# rocketpin.net
KiCad netlist of a schematic drawn in EAGLE
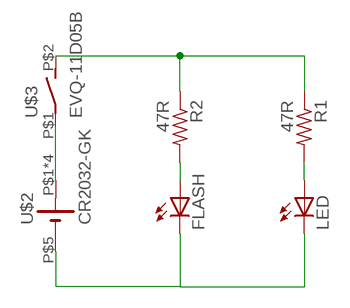
[diagram p0: schematic, sheet 1]

(export (version "E")
  (design (tool "Eeschema 10.0.6"))
  (components
    (comp (ref "FLASH")
      (value "LED5MM")
      (footprint "eagle-import:LED5MM")
      (libsource (lib "eagle-import") (part "LED5MM"))
    )
    (comp (ref "LED")
      (value "LED5MM")
      (footprint "eagle-import:LED5MM")
      (libsource (lib "eagle-import") (part "LED5MM"))
    )
    (comp (ref "R1")
      (value "47R")
      (footprint "eagle-import:0207_10")
      (libsource (lib "eagle-import") (part "R-US_0207/10"))
    )
    (comp (ref "R2")
      (value "47R")
      (footprint "eagle-import:0207_10")
      (libsource (lib "eagle-import") (part "R-US_0207/10"))
    )
    (comp (ref "U$2")
      (value "CR2032-GK")
      (footprint "eagle-import:BAT-HLD-001-THM")
      (libsource (lib "eagle-import") (part "CR2032-GK"))
    )
    (comp (ref "U$3")
      (value "EVQ-11D05B")
      (footprint "eagle-import:SPST-5MM")
      (libsource (lib "eagle-import") (part "EVQ-11D05B"))
    )
  )
  (nets
    (net (code "1") (name "Net-(FLASH-C)") (class "Default")
      (node (ref "FLASH") (pin "K") (pinfunction "C_K") (pintype "passive"))
      (node (ref "LED") (pin "K") (pinfunction "C_K") (pintype "passive"))
      (node (ref "U$2") (pin "P$5") (pinfunction "-_P$5") (pintype "passive"))
    )
    (net (code "2") (name "Net-(FLASH-PadA)") (class "Default")
      (node (ref "FLASH") (pin "A") (pinfunction "A_A") (pintype "passive"))
      (node (ref "R2") (pin "2") (pinfunction "2_2") (pintype "passive"))
    )
    (net (code "3") (name "Net-(LED-PadA)") (class "Default")
      (node (ref "LED") (pin "A") (pinfunction "A_A") (pintype "passive"))
      (node (ref "R1") (pin "2") (pinfunction "2_2") (pintype "passive"))
    )
    (net (code "4") (name "Net-(U$3-P)") (class "Default")
      (node (ref "U$2") (pin "P$1") (pinfunction "+_P$1") (pintype "passive"))
      (node (ref "U$2") (pin "P$2") (pinfunction "+_P$2") (pintype "passive"))
      (node (ref "U$2") (pin "P$3") (pinfunction "+_P$3") (pintype "passive"))
      (node (ref "U$2") (pin "P$4") (pinfunction "+_P$4") (pintype "passive"))
      (node (ref "U$3") (pin "P$1") (pinfunction "P_P$1") (pintype "passive"))
    )
    (net (code "5") (name "Net-(U$3-S)") (class "Default")
      (node (ref "R1") (pin "1") (pinfunction "1_1") (pintype "passive"))
      (node (ref "R2") (pin "1") (pinfunction "1_1") (pintype "passive"))
      (node (ref "U$3") (pin "P$2") (pinfunction "S_P$2") (pintype "passive"))
    )
  )
)
